# LED_panel.net
KiCad netlist of a schematic drawn in EAGLE
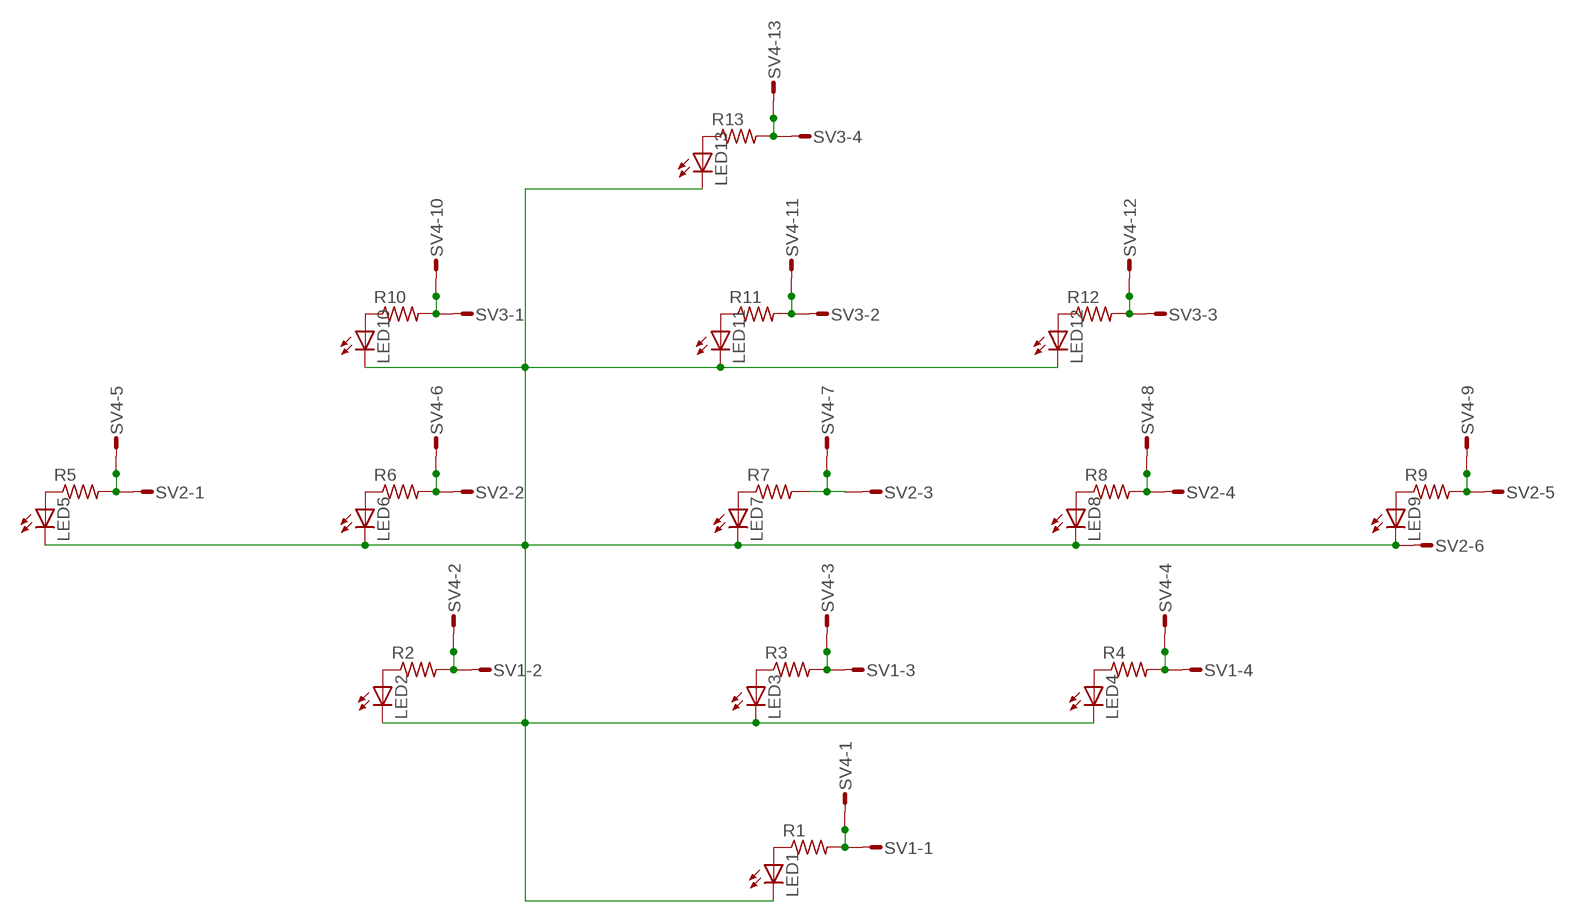
[diagram p0: schematic, sheet 1]

(export (version "E")
  (design (tool "Eeschema 10.0.6"))
  (components
    (comp (ref "LED1")
      (value "LED5MM")
      (footprint "eagle-import:LED5MM")
      (libsource (lib "eagle-import") (part "LED5MM"))
    )
    (comp (ref "LED2")
      (value "LED5MM")
      (footprint "eagle-import:LED5MM")
      (libsource (lib "eagle-import") (part "LED5MM"))
    )
    (comp (ref "LED3")
      (value "LED5MM")
      (footprint "eagle-import:LED5MM")
      (libsource (lib "eagle-import") (part "LED5MM"))
    )
    (comp (ref "LED4")
      (value "LED5MM")
      (footprint "eagle-import:LED5MM")
      (libsource (lib "eagle-import") (part "LED5MM"))
    )
    (comp (ref "LED5")
      (value "LED5MM")
      (footprint "eagle-import:LED5MM")
      (libsource (lib "eagle-import") (part "LED5MM"))
    )
    (comp (ref "LED6")
      (value "LED5MM")
      (footprint "eagle-import:LED5MM")
      (libsource (lib "eagle-import") (part "LED5MM"))
    )
    (comp (ref "LED7")
      (value "LED5MM")
      (footprint "eagle-import:LED5MM")
      (libsource (lib "eagle-import") (part "LED5MM"))
    )
    (comp (ref "LED8")
      (value "LED5MM")
      (footprint "eagle-import:LED5MM")
      (libsource (lib "eagle-import") (part "LED5MM"))
    )
    (comp (ref "LED9")
      (value "LED5MM")
      (footprint "eagle-import:LED5MM")
      (libsource (lib "eagle-import") (part "LED5MM"))
    )
    (comp (ref "LED10")
      (value "LED5MM")
      (footprint "eagle-import:LED5MM")
      (libsource (lib "eagle-import") (part "LED5MM"))
    )
    (comp (ref "LED11")
      (value "LED5MM")
      (footprint "eagle-import:LED5MM")
      (libsource (lib "eagle-import") (part "LED5MM"))
    )
    (comp (ref "LED12")
      (value "LED5MM")
      (footprint "eagle-import:LED5MM")
      (libsource (lib "eagle-import") (part "LED5MM"))
    )
    (comp (ref "LED13")
      (value "LED5MM")
      (footprint "eagle-import:LED5MM")
      (libsource (lib "eagle-import") (part "LED5MM"))
    )
    (comp (ref "R1")
      (value "R-US_0204/5")
      (footprint "eagle-import:0204_5")
      (libsource (lib "eagle-import") (part "R-US_0204/5"))
    )
    (comp (ref "R2")
      (value "R-US_0204/5")
      (footprint "eagle-import:0204_5")
      (libsource (lib "eagle-import") (part "R-US_0204/5"))
    )
    (comp (ref "R3")
      (value "R-US_0204/5")
      (footprint "eagle-import:0204_5")
      (libsource (lib "eagle-import") (part "R-US_0204/5"))
    )
    (comp (ref "R4")
      (value "R-US_0204/5")
      (footprint "eagle-import:0204_5")
      (libsource (lib "eagle-import") (part "R-US_0204/5"))
    )
    (comp (ref "R5")
      (value "R-US_0204/5")
      (footprint "eagle-import:0204_5")
      (libsource (lib "eagle-import") (part "R-US_0204/5"))
    )
    (comp (ref "R6")
      (value "R-US_0204/5")
      (footprint "eagle-import:0204_5")
      (libsource (lib "eagle-import") (part "R-US_0204/5"))
    )
    (comp (ref "R7")
      (value "R-US_0204/5")
      (footprint "eagle-import:0204_5")
      (libsource (lib "eagle-import") (part "R-US_0204/5"))
    )
    (comp (ref "R8")
      (value "R-US_0204/5")
      (footprint "eagle-import:0204_5")
      (libsource (lib "eagle-import") (part "R-US_0204/5"))
    )
    (comp (ref "R9")
      (value "R-US_0204/5")
      (footprint "eagle-import:0204_5")
      (libsource (lib "eagle-import") (part "R-US_0204/5"))
    )
    (comp (ref "R10")
      (value "R-US_0204/5")
      (footprint "eagle-import:0204_5")
      (libsource (lib "eagle-import") (part "R-US_0204/5"))
    )
    (comp (ref "R11")
      (value "R-US_0204/5")
      (footprint "eagle-import:0204_5")
      (libsource (lib "eagle-import") (part "R-US_0204/5"))
    )
    (comp (ref "R12")
      (value "R-US_0204/5")
      (footprint "eagle-import:0204_5")
      (libsource (lib "eagle-import") (part "R-US_0204/5"))
    )
    (comp (ref "R13")
      (value "R-US_0204/5")
      (footprint "eagle-import:0204_5")
      (libsource (lib "eagle-import") (part "R-US_0204/5"))
    )
    (comp (ref "SV1")
      (value "L04P")
      (footprint "eagle-import:L04P")
      (libsource (lib "eagle-import") (part "L04P"))
    )
    (comp (ref "SV2")
      (value "L06P")
      (footprint "eagle-import:L06P")
      (libsource (lib "eagle-import") (part "L06P"))
    )
    (comp (ref "SV3")
      (value "L04P")
      (footprint "eagle-import:L04P")
      (libsource (lib "eagle-import") (part "L04P"))
    )
    (comp (ref "SV4")
      (value "L13P")
      (footprint "eagle-import:L13P")
      (libsource (lib "eagle-import") (part "L13P"))
    )
  )
  (nets
    (net (code "1") (name "Net-(LED1-C)") (class "Default")
      (node (ref "LED1") (pin "K") (pinfunction "C_K") (pintype "passive"))
      (node (ref "LED10") (pin "K") (pinfunction "C_K") (pintype "passive"))
      (node (ref "LED11") (pin "K") (pinfunction "C_K") (pintype "passive"))
      (node (ref "LED12") (pin "K") (pinfunction "C_K") (pintype "passive"))
      (node (ref "LED13") (pin "K") (pinfunction "C_K") (pintype "passive"))
      (node (ref "LED2") (pin "K") (pinfunction "C_K") (pintype "passive"))
      (node (ref "LED3") (pin "K") (pinfunction "C_K") (pintype "passive"))
      (node (ref "LED4") (pin "K") (pinfunction "C_K") (pintype "passive"))
      (node (ref "LED5") (pin "K") (pinfunction "C_K") (pintype "passive"))
      (node (ref "LED6") (pin "K") (pinfunction "C_K") (pintype "passive"))
      (node (ref "LED7") (pin "K") (pinfunction "C_K") (pintype "passive"))
      (node (ref "LED8") (pin "K") (pinfunction "C_K") (pintype "passive"))
      (node (ref "LED9") (pin "K") (pinfunction "C_K") (pintype "passive"))
      (node (ref "SV2") (pin "6") (pinfunction "S_6") (pintype "passive"))
    )
    (net (code "2") (name "Net-(LED1-PadA)") (class "Default")
      (node (ref "LED1") (pin "A") (pinfunction "A_A") (pintype "passive"))
      (node (ref "R1") (pin "1") (pinfunction "1_1") (pintype "passive"))
    )
    (net (code "3") (name "Net-(LED2-PadA)") (class "Default")
      (node (ref "LED2") (pin "A") (pinfunction "A_A") (pintype "passive"))
      (node (ref "R2") (pin "1") (pinfunction "1_1") (pintype "passive"))
    )
    (net (code "4") (name "Net-(LED3-PadA)") (class "Default")
      (node (ref "LED3") (pin "A") (pinfunction "A_A") (pintype "passive"))
      (node (ref "R3") (pin "1") (pinfunction "1_1") (pintype "passive"))
    )
    (net (code "5") (name "Net-(LED4-PadA)") (class "Default")
      (node (ref "LED4") (pin "A") (pinfunction "A_A") (pintype "passive"))
      (node (ref "R4") (pin "1") (pinfunction "1_1") (pintype "passive"))
    )
    (net (code "6") (name "Net-(LED5-PadA)") (class "Default")
      (node (ref "LED5") (pin "A") (pinfunction "A_A") (pintype "passive"))
      (node (ref "R5") (pin "1") (pinfunction "1_1") (pintype "passive"))
    )
    (net (code "7") (name "Net-(LED6-PadA)") (class "Default")
      (node (ref "LED6") (pin "A") (pinfunction "A_A") (pintype "passive"))
      (node (ref "R6") (pin "1") (pinfunction "1_1") (pintype "passive"))
    )
    (net (code "8") (name "Net-(LED7-PadA)") (class "Default")
      (node (ref "LED7") (pin "A") (pinfunction "A_A") (pintype "passive"))
      (node (ref "R7") (pin "1") (pinfunction "1_1") (pintype "passive"))
    )
    (net (code "9") (name "Net-(LED8-PadA)") (class "Default")
      (node (ref "LED8") (pin "A") (pinfunction "A_A") (pintype "passive"))
      (node (ref "R8") (pin "1") (pinfunction "1_1") (pintype "passive"))
    )
    (net (code "10") (name "Net-(LED9-PadA)") (class "Default")
      (node (ref "LED9") (pin "A") (pinfunction "A_A") (pintype "passive"))
      (node (ref "R9") (pin "1") (pinfunction "1_1") (pintype "passive"))
    )
    (net (code "11") (name "Net-(LED10-PadA)") (class "Default")
      (node (ref "LED10") (pin "A") (pinfunction "A_A") (pintype "passive"))
      (node (ref "R10") (pin "1") (pinfunction "1_1") (pintype "passive"))
    )
    (net (code "12") (name "Net-(LED11-PadA)") (class "Default")
      (node (ref "LED11") (pin "A") (pinfunction "A_A") (pintype "passive"))
      (node (ref "R11") (pin "1") (pinfunction "1_1") (pintype "passive"))
    )
    (net (code "13") (name "Net-(LED12-PadA)") (class "Default")
      (node (ref "LED12") (pin "A") (pinfunction "A_A") (pintype "passive"))
      (node (ref "R12") (pin "1") (pinfunction "1_1") (pintype "passive"))
    )
    (net (code "14") (name "Net-(LED13-PadA)") (class "Default")
      (node (ref "LED13") (pin "A") (pinfunction "A_A") (pintype "passive"))
      (node (ref "R13") (pin "1") (pinfunction "1_1") (pintype "passive"))
    )
    (net (code "15") (name "Net-(SV1A-S)") (class "Default")
      (node (ref "R1") (pin "2") (pinfunction "2_2") (pintype "passive"))
      (node (ref "SV1") (pin "1") (pinfunction "S_1") (pintype "passive"))
      (node (ref "SV4") (pin "1") (pinfunction "S_1") (pintype "passive"))
    )
    (net (code "16") (name "Net-(SV1B-S)") (class "Default")
      (node (ref "R2") (pin "2") (pinfunction "2_2") (pintype "passive"))
      (node (ref "SV1") (pin "2") (pinfunction "S_2") (pintype "passive"))
      (node (ref "SV4") (pin "2") (pinfunction "S_2") (pintype "passive"))
    )
    (net (code "17") (name "Net-(SV1C-S)") (class "Default")
      (node (ref "R3") (pin "2") (pinfunction "2_2") (pintype "passive"))
      (node (ref "SV1") (pin "3") (pinfunction "S_3") (pintype "passive"))
      (node (ref "SV4") (pin "3") (pinfunction "S_3") (pintype "passive"))
    )
    (net (code "18") (name "Net-(SV1D-S)") (class "Default")
      (node (ref "R4") (pin "2") (pinfunction "2_2") (pintype "passive"))
      (node (ref "SV1") (pin "4") (pinfunction "S_4") (pintype "passive"))
      (node (ref "SV4") (pin "4") (pinfunction "S_4") (pintype "passive"))
    )
    (net (code "19") (name "Net-(SV2A-S)") (class "Default")
      (node (ref "R5") (pin "2") (pinfunction "2_2") (pintype "passive"))
      (node (ref "SV2") (pin "1") (pinfunction "S_1") (pintype "passive"))
      (node (ref "SV4") (pin "5") (pinfunction "S_5") (pintype "passive"))
    )
    (net (code "20") (name "Net-(SV2B-S)") (class "Default")
      (node (ref "R6") (pin "2") (pinfunction "2_2") (pintype "passive"))
      (node (ref "SV2") (pin "2") (pinfunction "S_2") (pintype "passive"))
      (node (ref "SV4") (pin "6") (pinfunction "S_6") (pintype "passive"))
    )
    (net (code "21") (name "Net-(SV2C-S)") (class "Default")
      (node (ref "R7") (pin "2") (pinfunction "2_2") (pintype "passive"))
      (node (ref "SV2") (pin "3") (pinfunction "S_3") (pintype "passive"))
      (node (ref "SV4") (pin "7") (pinfunction "S_7") (pintype "passive"))
    )
    (net (code "22") (name "Net-(SV2D-S)") (class "Default")
      (node (ref "R8") (pin "2") (pinfunction "2_2") (pintype "passive"))
      (node (ref "SV2") (pin "4") (pinfunction "S_4") (pintype "passive"))
      (node (ref "SV4") (pin "8") (pinfunction "S_8") (pintype "passive"))
    )
    (net (code "23") (name "Net-(SV2E-S)") (class "Default")
      (node (ref "R9") (pin "2") (pinfunction "2_2") (pintype "passive"))
      (node (ref "SV2") (pin "5") (pinfunction "S_5") (pintype "passive"))
      (node (ref "SV4") (pin "9") (pinfunction "S_9") (pintype "passive"))
    )
    (net (code "24") (name "Net-(SV3A-S)") (class "Default")
      (node (ref "R10") (pin "2") (pinfunction "2_2") (pintype "passive"))
      (node (ref "SV3") (pin "1") (pinfunction "S_1") (pintype "passive"))
      (node (ref "SV4") (pin "10") (pinfunction "S_10") (pintype "passive"))
    )
    (net (code "25") (name "Net-(SV3B-S)") (class "Default")
      (node (ref "R11") (pin "2") (pinfunction "2_2") (pintype "passive"))
      (node (ref "SV3") (pin "2") (pinfunction "S_2") (pintype "passive"))
      (node (ref "SV4") (pin "11") (pinfunction "S_11") (pintype "passive"))
    )
    (net (code "26") (name "Net-(SV3C-S)") (class "Default")
      (node (ref "R12") (pin "2") (pinfunction "2_2") (pintype "passive"))
      (node (ref "SV3") (pin "3") (pinfunction "S_3") (pintype "passive"))
      (node (ref "SV4") (pin "12") (pinfunction "S_12") (pintype "passive"))
    )
    (net (code "27") (name "Net-(SV3D-S)") (class "Default")
      (node (ref "R13") (pin "2") (pinfunction "2_2") (pintype "passive"))
      (node (ref "SV3") (pin "4") (pinfunction "S_4") (pintype "passive"))
      (node (ref "SV4") (pin "13") (pinfunction "S_13") (pintype "passive"))
    )
  )
)
